# Natcar.net
KiCad netlist of a schematic drawn in EAGLE
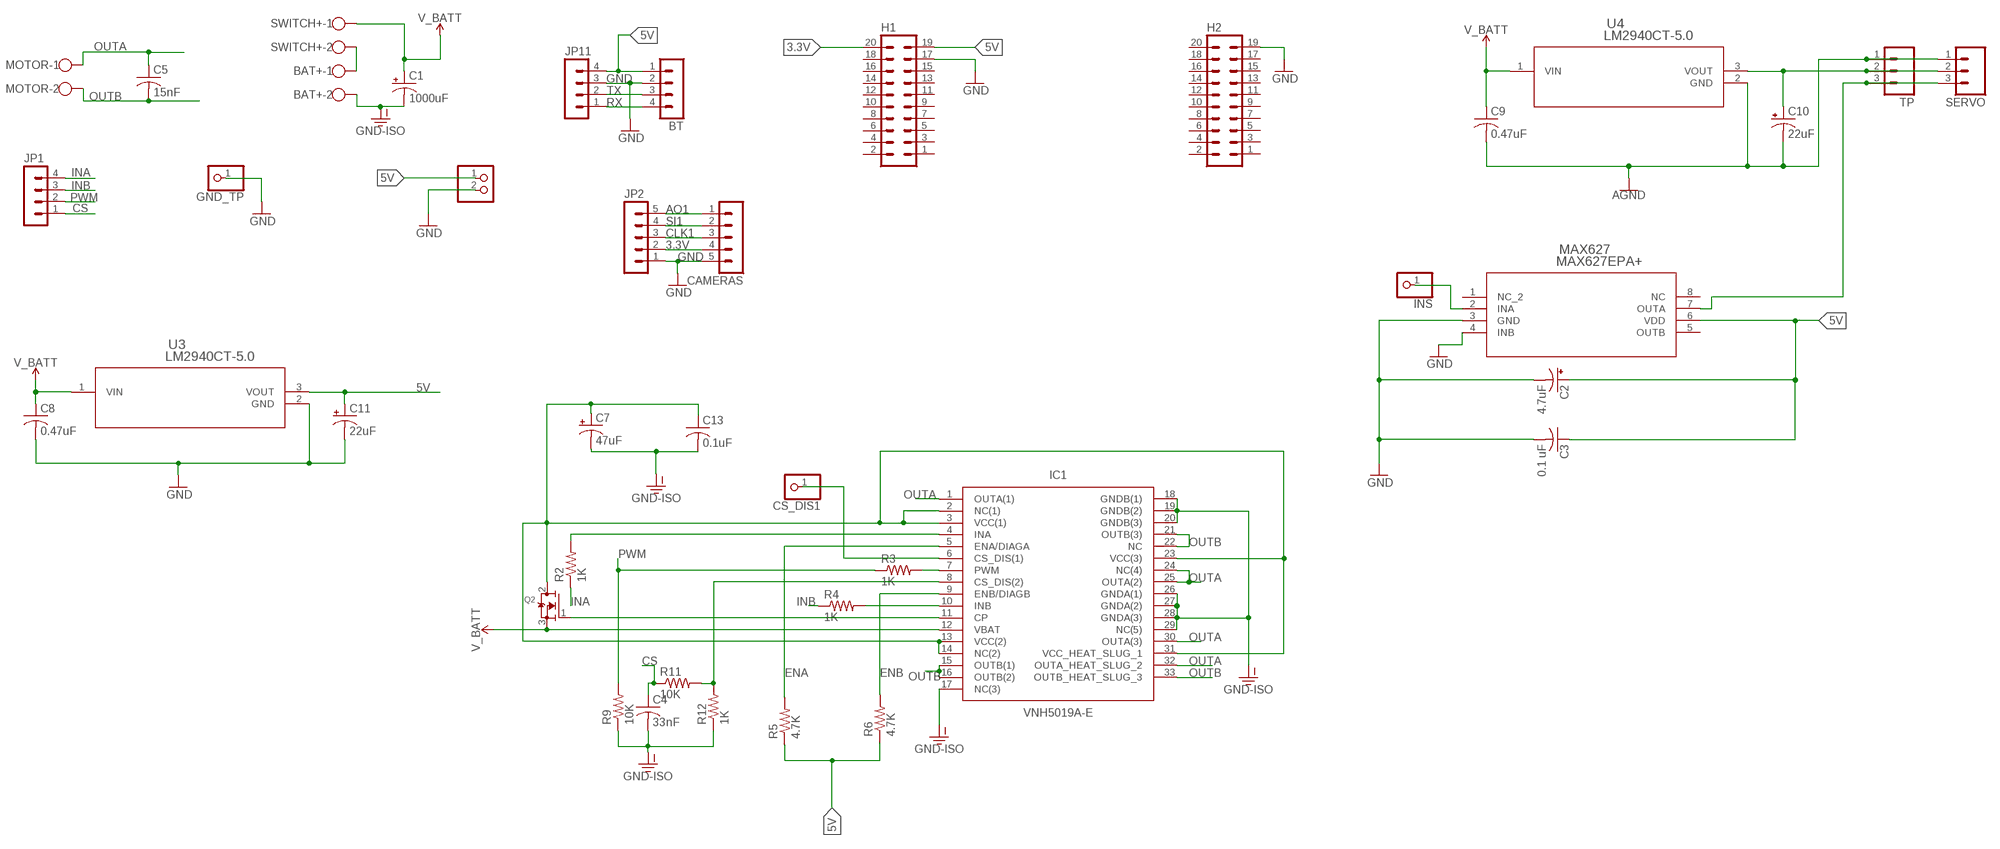
[diagram p0: schematic, sheet 1]

(export (version "E")
  (design (tool "Eeschema 10.0.6"))
  (components
    (comp (ref "BAT+")
      (value "W237-102")
      (footprint "eagle-import:W237-102")
      (fields (field (name "MPN") "237-102"))
      (libsource (lib "eagle-import") (part "W237-102"))
    )
    (comp (ref "BT")
      (value "MA04-1")
      (footprint "eagle-import:MA04-1")
      (libsource (lib "eagle-import") (part "con-lstb_162_MA04-1"))
    )
    (comp (ref "C1")
      (value "1000uF")
      (footprint "eagle-import:E5-10,5")
      (libsource (lib "eagle-import") (part "CPOL-USE5-10.5"))
    )
    (comp (ref "C2")
      (value "4.7uF")
      (footprint "eagle-import:E2-5")
      (libsource (lib "eagle-import") (part "CPOL-USE2-5"))
    )
    (comp (ref "C3")
      (value "0.1 uF")
      (footprint "eagle-import:C025-030X050")
      (libsource (lib "eagle-import") (part "C-US025-030X050"))
    )
    (comp (ref "C4")
      (value "33nF")
      (footprint "eagle-import:C025-030X050")
      (libsource (lib "eagle-import") (part "rcl_334_C-US025-030X050"))
    )
    (comp (ref "C5")
      (value "15nF")
      (footprint "eagle-import:C025-030X050")
      (libsource (lib "eagle-import") (part "rcl_334_C-US025-030X050"))
    )
    (comp (ref "C7")
      (value "47uF")
      (footprint "eagle-import:E2,5-5")
      (libsource (lib "eagle-import") (part "CPOL-USE2.5-5"))
    )
    (comp (ref "C8")
      (value "0.47uF")
      (footprint "eagle-import:C025-030X050")
      (libsource (lib "eagle-import") (part "rcl_334_C-US025-030X050"))
    )
    (comp (ref "C9")
      (value "0.47uF")
      (footprint "eagle-import:C025-030X050")
      (libsource (lib "eagle-import") (part "rcl_334_C-US025-030X050"))
    )
    (comp (ref "C10")
      (value "22uF")
      (footprint "eagle-import:E2,5-5")
      (libsource (lib "eagle-import") (part "CPOL-USE2.5-5"))
    )
    (comp (ref "C11")
      (value "22uF")
      (footprint "eagle-import:E2,5-5")
      (libsource (lib "eagle-import") (part "CPOL-USE2.5-5"))
    )
    (comp (ref "C13")
      (value "0.1uF")
      (footprint "eagle-import:C025-030X050")
      (libsource (lib "eagle-import") (part "rcl_334_C-US025-030X050"))
    )
    (comp (ref "CAMERAS")
      (value "MA05-1")
      (footprint "eagle-import:MA05-1")
      (libsource (lib "eagle-import") (part "MA05-1"))
    )
    (comp (ref "CS_DIS1")
      (value "PINHD-1X1")
      (footprint "eagle-import:1X01")
      (libsource (lib "eagle-import") (part "PINHD-1X1"))
    )
    (comp (ref "GND_TP")
      (value "PINHD-1X1")
      (footprint "eagle-import:1X01")
      (libsource (lib "eagle-import") (part "PINHD-1X1"))
    )
    (comp (ref "H1")
      (value "MA10-2")
      (footprint "eagle-import:MA10-2")
      (libsource (lib "eagle-import") (part "MA10-2"))
    )
    (comp (ref "H2")
      (value "MA10-2")
      (footprint "eagle-import:MA10-2")
      (libsource (lib "eagle-import") (part "MA10-2"))
    )
    (comp (ref "IC1")
      (value "VNH5019A-E")
      (footprint "eagle-import:VNH5019A-E_1")
      (fields (field (name "RS_PART_NUMBER") "8805550P"))
      (libsource (lib "eagle-import") (part "VNH5019A-E"))
    )
    (comp (ref "INS")
      (value "PINHD-1X1")
      (footprint "eagle-import:1X01")
      (libsource (lib "eagle-import") (part "PINHD-1X1"))
    )
    (comp (ref "JP1")
      (value "MA04-1")
      (footprint "eagle-import:MA04-1")
      (libsource (lib "eagle-import") (part "MA04-1"))
    )
    (comp (ref "JP2")
      (value "MA05-1")
      (footprint "eagle-import:MA05-1")
      (libsource (lib "eagle-import") (part "MA05-1"))
    )
    (comp (ref "JP11")
      (value "MA04-1")
      (footprint "eagle-import:MA04-1")
      (libsource (lib "eagle-import") (part "MA04-1"))
    )
    (comp (ref "JP12")
      (value "PINHD-1X2")
      (footprint "eagle-import:1X02")
      (libsource (lib "eagle-import") (part "PINHD-1X2"))
    )
    (comp (ref "MAX627")
      (value "MAX627EPA+")
      (footprint "eagle-import:21-0043D_8")
      (libsource (lib "eagle-import") (part "MAX627EPA+"))
    )
    (comp (ref "MOTOR")
      (value "W237-102")
      (footprint "eagle-import:W237-102")
      (fields (field (name "MPN") "237-102"))
      (libsource (lib "eagle-import") (part "con-wago-500_195_W237-102"))
    )
    (comp (ref "Q2")
      (value "MOSFET-NGDS_TO220V")
      (footprint "eagle-import:TO220V")
      (libsource (lib "eagle-import") (part "MOSFET-NGDS_TO220V"))
    )
    (comp (ref "R2")
      (value "1K")
      (footprint "eagle-import:0309_10")
      (libsource (lib "eagle-import") (part "R-US_0309/10"))
    )
    (comp (ref "R3")
      (value "1K")
      (footprint "eagle-import:0309_10")
      (libsource (lib "eagle-import") (part "R-US_0309/10"))
    )
    (comp (ref "R4")
      (value "1K")
      (footprint "eagle-import:0309_10")
      (libsource (lib "eagle-import") (part "R-US_0309/10"))
    )
    (comp (ref "R5")
      (value "4.7K")
      (footprint "eagle-import:0309_10")
      (libsource (lib "eagle-import") (part "R-US_0309/10"))
    )
    (comp (ref "R6")
      (value "4.7K")
      (footprint "eagle-import:0309_10")
      (libsource (lib "eagle-import") (part "R-US_0309/10"))
    )
    (comp (ref "R9")
      (value "10K")
      (footprint "eagle-import:0309_10")
      (libsource (lib "eagle-import") (part "R-US_0309/10"))
    )
    (comp (ref "R11")
      (value "10K")
      (footprint "eagle-import:0309_10")
      (libsource (lib "eagle-import") (part "R-US_0309/10"))
    )
    (comp (ref "R12")
      (value "1K")
      (footprint "eagle-import:0309_10")
      (libsource (lib "eagle-import") (part "R-US_0309/10"))
    )
    (comp (ref "SERVO")
      (value "MA03")
      (footprint "eagle-import:03P")
      (libsource (lib "eagle-import") (part "MA03"))
    )
    (comp (ref "SWITCH+")
      (value "W237-102")
      (footprint "eagle-import:W237-102")
      (fields (field (name "MPN") "237-102"))
      (libsource (lib "eagle-import") (part "W237-102"))
    )
    (comp (ref "TP")
      (value "MA03")
      (footprint "eagle-import:03P")
      (libsource (lib "eagle-import") (part "MA03"))
    )
    (comp (ref "U3")
      (value "LM2940CT-5.0")
      (footprint "eagle-import:T03B")
      (fields (field (name "MANUFACTURER_PART_NUMBER") "LM2940CT5.0"))
      (libsource (lib "eagle-import") (part "LM2940CT-5.0"))
    )
    (comp (ref "U4")
      (value "LM2940CT-5.0")
      (footprint "eagle-import:T03B")
      (fields (field (name "MANUFACTURER_PART_NUMBER") "LM2940CT5.0"))
      (libsource (lib "eagle-import") (part "LM2940CT-5.0"))
    )
  )
  (nets
    (net (code "1") (name "/AO1") (class "Default")
      (node (ref "CAMERAS") (pin "1") (pinfunction "1_1") (pintype "passive"))
      (node (ref "JP2") (pin "5") (pinfunction "5_5") (pintype "passive"))
    )
    (net (code "2") (name "/CLK1") (class "Default")
      (node (ref "CAMERAS") (pin "3") (pinfunction "3_3") (pintype "passive"))
      (node (ref "JP2") (pin "3") (pinfunction "3_3") (pintype "passive"))
    )
    (net (code "3") (name "/CS") (class "Default")
      (node (ref "C4") (pin "1") (pinfunction "1_1") (pintype "passive"))
      (node (ref "JP1") (pin "1") (pinfunction "1_1") (pintype "passive"))
      (node (ref "R11") (pin "1") (pinfunction "1_1") (pintype "passive"))
    )
    (net (code "4") (name "/ENA") (class "Default")
      (node (ref "IC1") (pin "5") (pinfunction "ENA/DIAGA_5") (pintype "passive"))
      (node (ref "R5") (pin "2") (pinfunction "2_2") (pintype "passive"))
    )
    (net (code "5") (name "/ENB") (class "Default")
      (node (ref "IC1") (pin "9") (pinfunction "ENB/DIAGB_9") (pintype "passive"))
      (node (ref "R6") (pin "2") (pinfunction "2_2") (pintype "passive"))
    )
    (net (code "6") (name "/INA") (class "Default")
      (node (ref "JP1") (pin "4") (pinfunction "4_4") (pintype "passive"))
      (node (ref "R2") (pin "1") (pinfunction "1_1") (pintype "passive"))
    )
    (net (code "7") (name "/INB") (class "Default")
      (node (ref "JP1") (pin "3") (pinfunction "3_3") (pintype "passive"))
      (node (ref "R4") (pin "1") (pinfunction "1_1") (pintype "passive"))
    )
    (net (code "8") (name "/OUTA") (class "Default")
      (node (ref "C5") (pin "1") (pinfunction "1_1") (pintype "passive"))
      (node (ref "IC1") (pin "1") (pinfunction "OUTA(1)_1") (pintype "bidirectional"))
      (node (ref "IC1") (pin "24") (pinfunction "NC(4)_24") (pintype "passive"))
      (node (ref "IC1") (pin "25") (pinfunction "OUTA(2)_25") (pintype "bidirectional"))
      (node (ref "IC1") (pin "30") (pinfunction "OUTA(3)_30") (pintype "bidirectional"))
      (node (ref "IC1") (pin "32") (pinfunction "OUTA_HEAT_SLUG_2_32") (pintype "bidirectional"))
      (node (ref "MOTOR") (pin "1") (pinfunction "KL_1") (pintype "passive"))
    )
    (net (code "9") (name "/OUTB") (class "Default")
      (node (ref "C5") (pin "2") (pinfunction "2_2") (pintype "passive"))
      (node (ref "IC1") (pin "15") (pinfunction "OUTB(1)_15") (pintype "bidirectional"))
      (node (ref "IC1") (pin "16") (pinfunction "OUTB(2)_16") (pintype "bidirectional"))
      (node (ref "IC1") (pin "21") (pinfunction "OUTB(3)_21") (pintype "bidirectional"))
      (node (ref "IC1") (pin "22") (pinfunction "NC_22") (pintype "passive"))
      (node (ref "IC1") (pin "33") (pinfunction "OUTB_HEAT_SLUG_3_33") (pintype "bidirectional"))
      (node (ref "MOTOR") (pin "2") (pinfunction "KL_2") (pintype "passive"))
    )
    (net (code "10") (name "/PWM") (class "Default")
      (node (ref "JP1") (pin "2") (pinfunction "2_2") (pintype "passive"))
      (node (ref "R3") (pin "1") (pinfunction "1_1") (pintype "passive"))
      (node (ref "R9") (pin "2") (pinfunction "2_2") (pintype "passive"))
    )
    (net (code "11") (name "/RX") (class "Default")
      (node (ref "BT") (pin "4") (pinfunction "4_4") (pintype "passive"))
      (node (ref "JP11") (pin "1") (pinfunction "1_1") (pintype "passive"))
    )
    (net (code "12") (name "/SI1") (class "Default")
      (node (ref "CAMERAS") (pin "2") (pinfunction "2_2") (pintype "passive"))
      (node (ref "JP2") (pin "4") (pinfunction "4_4") (pintype "passive"))
    )
    (net (code "13") (name "/TX") (class "Default")
      (node (ref "BT") (pin "3") (pinfunction "3_3") (pintype "passive"))
      (node (ref "JP11") (pin "2") (pinfunction "2_2") (pintype "passive"))
    )
    (net (code "14") (name "3.3V") (class "Default")
      (node (ref "CAMERAS") (pin "4") (pinfunction "4_4") (pintype "passive"))
      (node (ref "H1") (pin "20") (pinfunction "20_20") (pintype "passive"))
      (node (ref "JP2") (pin "2") (pinfunction "2_2") (pintype "passive"))
    )
    (net (code "15") (name "5V") (class "Default")
      (node (ref "BT") (pin "1") (pinfunction "1_1") (pintype "passive"))
      (node (ref "C11") (pin "+") (pinfunction "+_+") (pintype "passive"))
      (node (ref "C2") (pin "+") (pinfunction "+_+") (pintype "passive"))
      (node (ref "C3") (pin "1") (pinfunction "1_1") (pintype "passive"))
      (node (ref "H1") (pin "19") (pinfunction "19_19") (pintype "passive"))
      (node (ref "JP11") (pin "4") (pinfunction "4_4") (pintype "passive"))
      (node (ref "JP12") (pin "1") (pinfunction "1_1") (pintype "passive"))
      (node (ref "MAX627") (pin "6") (pinfunction "VDD_6") (pintype "power_in"))
      (node (ref "R5") (pin "1") (pinfunction "1_1") (pintype "passive"))
      (node (ref "R6") (pin "1") (pinfunction "1_1") (pintype "passive"))
      (node (ref "U3") (pin "3") (pinfunction "VOUT_3") (pintype "output"))
    )
    (net (code "16") (name "AGND") (class "Default")
      (node (ref "C10") (pin "-") (pinfunction "-_-") (pintype "passive"))
      (node (ref "C9") (pin "2") (pinfunction "2_2") (pintype "passive"))
      (node (ref "SERVO") (pin "1") (pinfunction "1_1") (pintype "passive"))
      (node (ref "TP") (pin "1") (pinfunction "1_1") (pintype "passive"))
      (node (ref "U4") (pin "2") (pinfunction "GND_2") (pintype "passive"))
    )
    (net (code "17") (name "GND") (class "Default")
      (node (ref "BT") (pin "2") (pinfunction "2_2") (pintype "passive"))
      (node (ref "C11") (pin "-") (pinfunction "-_-") (pintype "passive"))
      (node (ref "C2") (pin "-") (pinfunction "-_-") (pintype "passive"))
      (node (ref "C3") (pin "2") (pinfunction "2_2") (pintype "passive"))
      (node (ref "C8") (pin "2") (pinfunction "2_2") (pintype "passive"))
      (node (ref "CAMERAS") (pin "5") (pinfunction "5_5") (pintype "passive"))
      (node (ref "GND_TP") (pin "1") (pinfunction "1_1") (pintype "passive"))
      (node (ref "H1") (pin "17") (pinfunction "17_17") (pintype "passive"))
      (node (ref "H2") (pin "19") (pinfunction "19_19") (pintype "passive"))
      (node (ref "JP11") (pin "3") (pinfunction "3_3") (pintype "passive"))
      (node (ref "JP12") (pin "2") (pinfunction "2_2") (pintype "passive"))
      (node (ref "JP2") (pin "1") (pinfunction "1_1") (pintype "passive"))
      (node (ref "MAX627") (pin "3") (pinfunction "GND_3") (pintype "power_in"))
      (node (ref "MAX627") (pin "4") (pinfunction "INB_4") (pintype "input"))
      (node (ref "U3") (pin "2") (pinfunction "GND_2") (pintype "passive"))
    )
    (net (code "18") (name "GND-ISO") (class "Default")
      (node (ref "BAT+") (pin "2") (pinfunction "KL_2") (pintype "passive"))
      (node (ref "C1") (pin "-") (pinfunction "-_-") (pintype "passive"))
      (node (ref "C13") (pin "2") (pinfunction "2_2") (pintype "passive"))
      (node (ref "C4") (pin "2") (pinfunction "2_2") (pintype "passive"))
      (node (ref "C7") (pin "-") (pinfunction "-_-") (pintype "passive"))
      (node (ref "IC1") (pin "17") (pinfunction "NC(3)_17") (pintype "passive"))
      (node (ref "IC1") (pin "18") (pinfunction "GNDB(1)_18") (pintype "power_in"))
      (node (ref "IC1") (pin "19") (pinfunction "GNDB(2)_19") (pintype "power_in"))
      (node (ref "IC1") (pin "20") (pinfunction "GNDB(3)_20") (pintype "power_in"))
      (node (ref "IC1") (pin "26") (pinfunction "GNDA(1)_26") (pintype "power_in"))
      (node (ref "IC1") (pin "27") (pinfunction "GNDA(2)_27") (pintype "power_in"))
      (node (ref "IC1") (pin "28") (pinfunction "GNDA(3)_28") (pintype "power_in"))
      (node (ref "IC1") (pin "29") (pinfunction "NC(5)_29") (pintype "passive"))
      (node (ref "R12") (pin "1") (pinfunction "1_1") (pintype "passive"))
      (node (ref "R9") (pin "1") (pinfunction "1_1") (pintype "passive"))
    )
    (net (code "19") (name "Net-(BAT+A-KL)") (class "Default")
      (node (ref "BAT+") (pin "1") (pinfunction "KL_1") (pintype "passive"))
      (node (ref "SWITCH+") (pin "2") (pinfunction "KL_2") (pintype "passive"))
    )
    (net (code "20") (name "Net-(IC1-CP)") (class "Default")
      (node (ref "IC1") (pin "11") (pinfunction "CP_11") (pintype "passive"))
      (node (ref "Q2") (pin "1") (pinfunction "G_1") (pintype "bidirectional"))
    )
    (net (code "21") (name "Net-(IC1-CS_DIS(1))") (class "Default")
      (node (ref "CS_DIS1") (pin "1") (pinfunction "1_1") (pintype "passive"))
      (node (ref "IC1") (pin "6") (pinfunction "CS_DIS(1)_6") (pintype "input"))
    )
    (net (code "22") (name "Net-(IC1-CS_DIS(2))") (class "Default")
      (node (ref "IC1") (pin "8") (pinfunction "CS_DIS(2)_8") (pintype "input"))
      (node (ref "R11") (pin "2") (pinfunction "2_2") (pintype "passive"))
      (node (ref "R12") (pin "2") (pinfunction "2_2") (pintype "passive"))
    )
    (net (code "23") (name "Net-(IC1-INA)") (class "Default")
      (node (ref "IC1") (pin "4") (pinfunction "INA_4") (pintype "input"))
      (node (ref "R2") (pin "2") (pinfunction "2_2") (pintype "passive"))
    )
    (net (code "24") (name "Net-(IC1-INB)") (class "Default")
      (node (ref "IC1") (pin "10") (pinfunction "INB_10") (pintype "input"))
      (node (ref "R4") (pin "2") (pinfunction "2_2") (pintype "passive"))
    )
    (net (code "25") (name "Net-(IC1-NC(1))") (class "Default")
      (node (ref "C13") (pin "1") (pinfunction "1_1") (pintype "passive"))
      (node (ref "C7") (pin "+") (pinfunction "+_+") (pintype "passive"))
      (node (ref "IC1") (pin "13") (pinfunction "VCC(2)_13") (pintype "power_in"))
      (node (ref "IC1") (pin "14") (pinfunction "NC(2)_14") (pintype "passive"))
      (node (ref "IC1") (pin "2") (pinfunction "NC(1)_2") (pintype "passive"))
      (node (ref "IC1") (pin "23") (pinfunction "VCC(3)_23") (pintype "power_in"))
      (node (ref "IC1") (pin "3") (pinfunction "VCC(1)_3") (pintype "power_in"))
      (node (ref "IC1") (pin "31") (pinfunction "VCC_HEAT_SLUG_1_31") (pintype "power_in"))
      (node (ref "Q2") (pin "2") (pinfunction "D_2") (pintype "bidirectional"))
    )
    (net (code "26") (name "Net-(IC1-PWM)") (class "Default")
      (node (ref "IC1") (pin "7") (pinfunction "PWM_7") (pintype "passive"))
      (node (ref "R3") (pin "2") (pinfunction "2_2") (pintype "passive"))
    )
    (net (code "27") (name "Net-(MAX627-INA)") (class "Default")
      (node (ref "INS") (pin "1") (pinfunction "1_1") (pintype "passive"))
      (node (ref "MAX627") (pin "2") (pinfunction "INA_2") (pintype "input"))
    )
    (net (code "28") (name "Net-(MAX627-OUTA)") (class "Default")
      (node (ref "MAX627") (pin "7") (pinfunction "OUTA_7") (pintype "output"))
      (node (ref "SERVO") (pin "3") (pinfunction "3_3") (pintype "passive"))
      (node (ref "TP") (pin "3") (pinfunction "3_3") (pintype "passive"))
    )
    (net (code "29") (name "Net-(U4-VOUT)") (class "Default")
      (node (ref "C10") (pin "+") (pinfunction "+_+") (pintype "passive"))
      (node (ref "SERVO") (pin "2") (pinfunction "2_2") (pintype "passive"))
      (node (ref "TP") (pin "2") (pinfunction "2_2") (pintype "passive"))
      (node (ref "U4") (pin "3") (pinfunction "VOUT_3") (pintype "output"))
    )
    (net (code "30") (name "V_BATT") (class "Default")
      (node (ref "C1") (pin "+") (pinfunction "+_+") (pintype "passive"))
      (node (ref "C8") (pin "1") (pinfunction "1_1") (pintype "passive"))
      (node (ref "C9") (pin "1") (pinfunction "1_1") (pintype "passive"))
      (node (ref "IC1") (pin "12") (pinfunction "VBAT_12") (pintype "passive"))
      (node (ref "Q2") (pin "3") (pinfunction "S_3") (pintype "bidirectional"))
      (node (ref "SWITCH+") (pin "1") (pinfunction "KL_1") (pintype "passive"))
      (node (ref "U3") (pin "1") (pinfunction "VIN_1") (pintype "input"))
      (node (ref "U4") (pin "1") (pinfunction "VIN_1") (pintype "input"))
    )
    (net (code "31") (name "unconnected-(H1-Pad1)") (class "Default")
      (node (ref "H1") (pin "1") (pinfunction "1_1") (pintype "passive"))
    )
    (net (code "32") (name "unconnected-(H1-Pad2)") (class "Default")
      (node (ref "H1") (pin "2") (pinfunction "2_2") (pintype "passive"))
    )
    (net (code "33") (name "unconnected-(H1-Pad3)") (class "Default")
      (node (ref "H1") (pin "3") (pinfunction "3_3") (pintype "passive"))
    )
    (net (code "34") (name "unconnected-(H1-Pad4)") (class "Default")
      (node (ref "H1") (pin "4") (pinfunction "4_4") (pintype "passive"))
    )
    (net (code "35") (name "unconnected-(H1-Pad5)") (class "Default")
      (node (ref "H1") (pin "5") (pinfunction "5_5") (pintype "passive"))
    )
    (net (code "36") (name "unconnected-(H1-Pad6)") (class "Default")
      (node (ref "H1") (pin "6") (pinfunction "6_6") (pintype "passive"))
    )
    (net (code "37") (name "unconnected-(H1-Pad7)") (class "Default")
      (node (ref "H1") (pin "7") (pinfunction "7_7") (pintype "passive"))
    )
    (net (code "38") (name "unconnected-(H1-Pad8)") (class "Default")
      (node (ref "H1") (pin "8") (pinfunction "8_8") (pintype "passive"))
    )
    (net (code "39") (name "unconnected-(H1-Pad9)") (class "Default")
      (node (ref "H1") (pin "9") (pinfunction "9_9") (pintype "passive"))
    )
    (net (code "40") (name "unconnected-(H1-Pad10)") (class "Default")
      (node (ref "H1") (pin "10") (pinfunction "10_10") (pintype "passive"))
    )
    (net (code "41") (name "unconnected-(H1-Pad11)") (class "Default")
      (node (ref "H1") (pin "11") (pinfunction "11_11") (pintype "passive"))
    )
    (net (code "42") (name "unconnected-(H1-Pad12)") (class "Default")
      (node (ref "H1") (pin "12") (pinfunction "12_12") (pintype "passive"))
    )
    (net (code "43") (name "unconnected-(H1-Pad13)") (class "Default")
      (node (ref "H1") (pin "13") (pinfunction "13_13") (pintype "passive"))
    )
    (net (code "44") (name "unconnected-(H1-Pad14)") (class "Default")
      (node (ref "H1") (pin "14") (pinfunction "14_14") (pintype "passive"))
    )
    (net (code "45") (name "unconnected-(H1-Pad15)") (class "Default")
      (node (ref "H1") (pin "15") (pinfunction "15_15") (pintype "passive"))
    )
    (net (code "46") (name "unconnected-(H1-Pad16)") (class "Default")
      (node (ref "H1") (pin "16") (pinfunction "16_16") (pintype "passive"))
    )
    (net (code "47") (name "unconnected-(H1-Pad18)") (class "Default")
      (node (ref "H1") (pin "18") (pinfunction "18_18") (pintype "passive"))
    )
    (net (code "48") (name "unconnected-(H2-Pad1)") (class "Default")
      (node (ref "H2") (pin "1") (pinfunction "1_1") (pintype "passive"))
    )
    (net (code "49") (name "unconnected-(H2-Pad2)") (class "Default")
      (node (ref "H2") (pin "2") (pinfunction "2_2") (pintype "passive"))
    )
    (net (code "50") (name "unconnected-(H2-Pad3)") (class "Default")
      (node (ref "H2") (pin "3") (pinfunction "3_3") (pintype "passive"))
    )
    (net (code "51") (name "unconnected-(H2-Pad4)") (class "Default")
      (node (ref "H2") (pin "4") (pinfunction "4_4") (pintype "passive"))
    )
    (net (code "52") (name "unconnected-(H2-Pad5)") (class "Default")
      (node (ref "H2") (pin "5") (pinfunction "5_5") (pintype "passive"))
    )
    (net (code "53") (name "unconnected-(H2-Pad6)") (class "Default")
      (node (ref "H2") (pin "6") (pinfunction "6_6") (pintype "passive"))
    )
    (net (code "54") (name "unconnected-(H2-Pad7)") (class "Default")
      (node (ref "H2") (pin "7") (pinfunction "7_7") (pintype "passive"))
    )
    (net (code "55") (name "unconnected-(H2-Pad8)") (class "Default")
      (node (ref "H2") (pin "8") (pinfunction "8_8") (pintype "passive"))
    )
    (net (code "56") (name "unconnected-(H2-Pad9)") (class "Default")
      (node (ref "H2") (pin "9") (pinfunction "9_9") (pintype "passive"))
    )
    (net (code "57") (name "unconnected-(H2-Pad10)") (class "Default")
      (node (ref "H2") (pin "10") (pinfunction "10_10") (pintype "passive"))
    )
    (net (code "58") (name "unconnected-(H2-Pad11)") (class "Default")
      (node (ref "H2") (pin "11") (pinfunction "11_11") (pintype "passive"))
    )
    (net (code "59") (name "unconnected-(H2-Pad12)") (class "Default")
      (node (ref "H2") (pin "12") (pinfunction "12_12") (pintype "passive"))
    )
    (net (code "60") (name "unconnected-(H2-Pad13)") (class "Default")
      (node (ref "H2") (pin "13") (pinfunction "13_13") (pintype "passive"))
    )
    (net (code "61") (name "unconnected-(H2-Pad14)") (class "Default")
      (node (ref "H2") (pin "14") (pinfunction "14_14") (pintype "passive"))
    )
    (net (code "62") (name "unconnected-(H2-Pad15)") (class "Default")
      (node (ref "H2") (pin "15") (pinfunction "15_15") (pintype "passive"))
    )
    (net (code "63") (name "unconnected-(H2-Pad16)") (class "Default")
      (node (ref "H2") (pin "16") (pinfunction "16_16") (pintype "passive"))
    )
    (net (code "64") (name "unconnected-(H2-Pad17)") (class "Default")
      (node (ref "H2") (pin "17") (pinfunction "17_17") (pintype "passive"))
    )
    (net (code "65") (name "unconnected-(H2-Pad18)") (class "Default")
      (node (ref "H2") (pin "18") (pinfunction "18_18") (pintype "passive"))
    )
    (net (code "66") (name "unconnected-(H2-Pad20)") (class "Default")
      (node (ref "H2") (pin "20") (pinfunction "20_20") (pintype "passive"))
    )
    (net (code "67") (name "unconnected-(MAX627-NC-Pad8)") (class "Default")
      (node (ref "MAX627") (pin "8") (pinfunction "NC_8") (pintype "no_connect"))
    )
    (net (code "68") (name "unconnected-(MAX627-NC_2-Pad1)") (class "Default")
      (node (ref "MAX627") (pin "1") (pinfunction "NC_2_1") (pintype "no_connect"))
    )
    (net (code "69") (name "unconnected-(MAX627-OUTB-Pad5)") (class "Default")
      (node (ref "MAX627") (pin "5") (pinfunction "OUTB_5") (pintype "output"))
    )
  )
)
